# AdaptadorUSBSerialRS232.net
KiCad netlist of a schematic drawn in Altium Designer
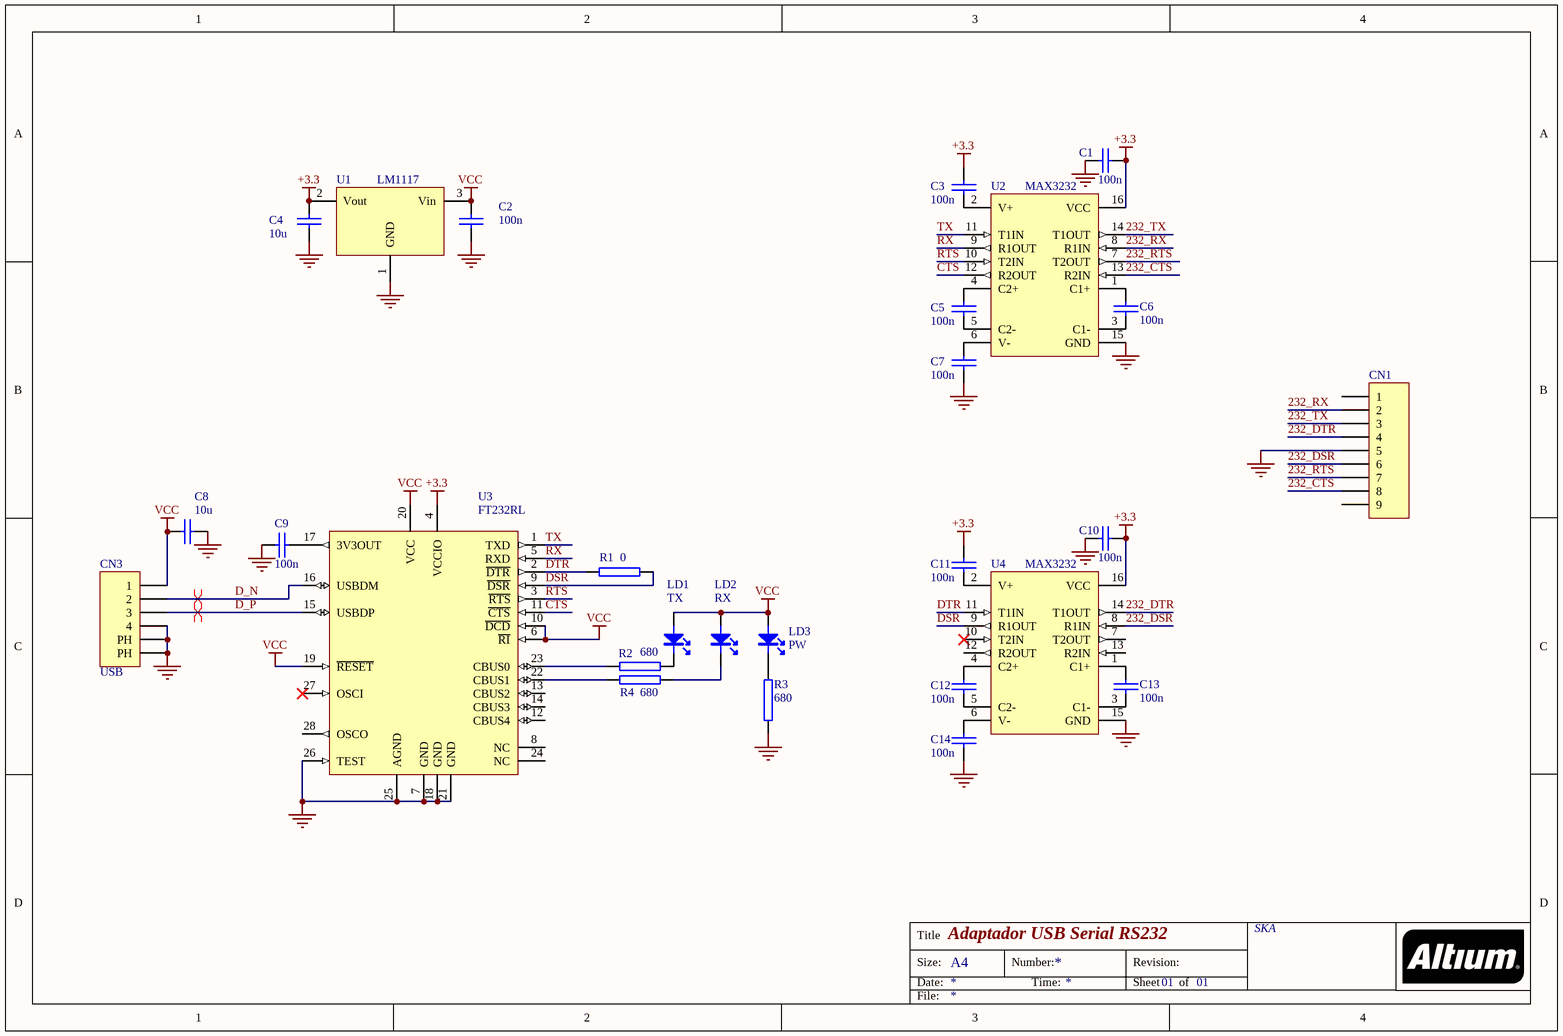
[diagram p0: AdaptadorUSBSerialRS232.SchDoc]

(export (version "E")
  (design (tool "Eeschema 10.0.6"))
  (components
    (comp (ref "C1")
      (value "100n")
      (footprint "0805C")
      (description "CAPACITOR SMD 0805 100nF/50V X7R")
      (libsource (lib "Básicos") (part "CAP"))
    )
    (comp (ref "C2")
      (value "100n")
      (footprint "0805C")
      (description "CAPACITOR SMD 0805 100nF/50V X7R")
      (libsource (lib "Básicos") (part "CAP"))
    )
    (comp (ref "C3")
      (value "100n")
      (footprint "0805C")
      (description "CAPACITOR SMD 0805 100nF/50V X7R")
      (libsource (lib "Básicos") (part "CAP"))
    )
    (comp (ref "C4")
      (value "10u")
      (footprint "0805C")
      (description "CAPACITOR SMD 0805 10UF/6,3V X7R")
      (libsource (lib "") (part "CAP_1"))
    )
    (comp (ref "C5")
      (value "100n")
      (footprint "0805C")
      (description "CAPACITOR SMD 0805 100nF/50V X7R")
      (libsource (lib "Básicos") (part "CAP"))
    )
    (comp (ref "C6")
      (value "100n")
      (footprint "0805C")
      (description "CAPACITOR SMD 0805 100nF/50V X7R")
      (libsource (lib "Básicos") (part "CAP"))
    )
    (comp (ref "C7")
      (value "100n")
      (footprint "0805C")
      (description "CAPACITOR SMD 0805 100nF/50V X7R")
      (libsource (lib "Básicos") (part "CAP"))
    )
    (comp (ref "C8")
      (value "10u")
      (footprint "0805C")
      (description "CAPACITOR SMD 0805 10UF/6,3V X7R")
      (libsource (lib "") (part "CAP_1"))
    )
    (comp (ref "C9")
      (value "100n")
      (footprint "0805C")
      (description "CAPACITOR SMD 0805 100NF/50V X7R")
      (libsource (lib "Básicos") (part "CAP"))
    )
    (comp (ref "C10")
      (value "100n")
      (footprint "0805C")
      (description "CAPACITOR SMD 0805 100nF/50V X7R")
      (libsource (lib "Básicos") (part "CAP"))
    )
    (comp (ref "C11")
      (value "100n")
      (footprint "0805C")
      (description "CAPACITOR SMD 0805 100nF/50V X7R")
      (libsource (lib "Básicos") (part "CAP"))
    )
    (comp (ref "C12")
      (value "100n")
      (footprint "0805C")
      (description "CAPACITOR SMD 0805 100nF/50V X7R")
      (libsource (lib "Básicos") (part "CAP"))
    )
    (comp (ref "C13")
      (value "100n")
      (footprint "0805C")
      (description "CAPACITOR SMD 0805 100nF/50V X7R")
      (libsource (lib "Básicos") (part "CAP"))
    )
    (comp (ref "C14")
      (value "100n")
      (footprint "0805C")
      (description "CAPACITOR SMD 0805 100nF/50V X7R")
      (libsource (lib "Básicos") (part "CAP"))
    )
    (comp (ref "CN1")
      (value "DB9M")
      (footprint "BARRA1X9")
      (description "Espera para DB9 M")
      (libsource (lib "Miscellaneous Connectors") (part "Header 9"))
    )
    (comp (ref "CN3")
      (value "USB")
      (footprint "USB-B 90")
      (description "CONECTOR USB")
      (libsource (lib "Miscellaneous Connectors") (part "Header 6"))
    )
    (comp (ref "LD1")
      (value "RED")
      (footprint "0805L")
      (description "LED 0805 VERMELHO")
      (fields (field (name "FUNCAO") "TX"))
      (libsource (lib "Opto") (part "LED"))
    )
    (comp (ref "LD2")
      (value "RED")
      (footprint "0805L")
      (description "LED 0805 VERMELHO")
      (fields (field (name "FUNCAO") "RX"))
      (libsource (lib "Opto") (part "LED"))
    )
    (comp (ref "LD3")
      (value "RED")
      (footprint "0805L")
      (description "LED 0805 VERMELHO")
      (fields (field (name "FUNCAO") "PW"))
      (libsource (lib "Opto") (part "LED"))
    )
    (comp (ref "R1")
      (value "0")
      (footprint "0805R")
      (description "RESISTOR SMD 0805 0 OHM (JUMPER)")
      (libsource (lib "Básicos") (part "RES"))
    )
    (comp (ref "R2")
      (value "680")
      (footprint "0805R")
      (description "RESISTOR SMD 0805 680 OHM")
      (libsource (lib "Básicos") (part "RES"))
    )
    (comp (ref "R3")
      (value "680")
      (footprint "0805R")
      (description "RESISTOR SMD 0805 680 OHM")
      (libsource (lib "") (part "RES_1"))
    )
    (comp (ref "R4")
      (value "680")
      (footprint "0805R")
      (description "RESISTOR SMD 0805 680 OHM")
      (libsource (lib "Básicos") (part "RES"))
    )
    (comp (ref "U1")
      (value "LM1117")
      (footprint "SOT223")
      (description "REGULADOR LINEAR SMD LM1117MPX-3.3")
      (libsource (lib "Regulador") (part "LM1117"))
    )
    (comp (ref "U2")
      (value "MAX3232")
      (footprint "SO16")
      (description "CI SMD MAX3232 SO16 NARROW")
      (libsource (lib "Interface") (part "MAX232"))
    )
    (comp (ref "U3")
      (value "FT232RL")
      (footprint "SSOP28-175-0.64")
      (description "USB UART FT232RL, SSOP-28, Tray")
      (libsource (lib "altium-import") (part "root_0_COM-UART-FT232R-IL28_"))
    )
    (comp (ref "U4")
      (value "MAX3232")
      (footprint "SO16")
      (description "CI SMD MAX3232 SO16 NARROW")
      (libsource (lib "Interface") (part "MAX232"))
    )
  )
  (nets
    (net (code "1") (name "+3.3") (class "Default")
      (node (ref "C1") (pin "1") (pinfunction "1_1") (pintype "passive"))
      (node (ref "C10") (pin "1") (pinfunction "1_1") (pintype "passive"))
      (node (ref "C11") (pin "1") (pinfunction "1_1") (pintype "passive"))
      (node (ref "C3") (pin "1") (pinfunction "1_1") (pintype "passive"))
      (node (ref "C4") (pin "1") (pinfunction "1_1") (pintype "passive"))
      (node (ref "U1") (pin "2") (pinfunction "Vout_2") (pintype "power_in"))
      (node (ref "U2") (pin "16") (pinfunction "VCC_16") (pintype "power_in"))
      (node (ref "U3") (pin "4") (pinfunction "VCCIO_4") (pintype "power_in"))
      (node (ref "U4") (pin "16") (pinfunction "VCC_16") (pintype "power_in"))
    )
    (net (code "2") (name "/232_CTS") (class "Default")
      (node (ref "CN1") (pin "8") (pinfunction "8_8") (pintype "passive"))
      (node (ref "U2") (pin "13") (pinfunction "R2IN_13") (pintype "input"))
    )
    (net (code "3") (name "/232_DSR") (class "Default")
      (node (ref "CN1") (pin "6") (pinfunction "6_6") (pintype "passive"))
      (node (ref "U4") (pin "8") (pinfunction "R1IN_8") (pintype "input"))
    )
    (net (code "4") (name "/232_DTR") (class "Default")
      (node (ref "CN1") (pin "4") (pinfunction "4_4") (pintype "passive"))
      (node (ref "U4") (pin "14") (pinfunction "T1OUT_14") (pintype "output"))
    )
    (net (code "5") (name "/232_RTS") (class "Default")
      (node (ref "CN1") (pin "7") (pinfunction "7_7") (pintype "passive"))
      (node (ref "U2") (pin "7") (pinfunction "T2OUT_7") (pintype "output"))
    )
    (net (code "6") (name "/232_RX") (class "Default")
      (node (ref "CN1") (pin "2") (pinfunction "2_2") (pintype "passive"))
      (node (ref "U2") (pin "8") (pinfunction "R1IN_8") (pintype "input"))
    )
    (net (code "7") (name "/232_TX") (class "Default")
      (node (ref "CN1") (pin "3") (pinfunction "3_3") (pintype "passive"))
      (node (ref "U2") (pin "14") (pinfunction "T1OUT_14") (pintype "output"))
    )
    (net (code "8") (name "/CTS") (class "Default")
      (node (ref "U2") (pin "12") (pinfunction "R2OUT_12") (pintype "output"))
      (node (ref "U3") (pin "11") (pinfunction "~{CTS}_11") (pintype "input"))
    )
    (net (code "9") (name "/DSR") (class "Default")
      (node (ref "R1") (pin "2") (pinfunction "2_2") (pintype "passive"))
      (node (ref "U3") (pin "9") (pinfunction "~{DSR}_9") (pintype "input"))
      (node (ref "U4") (pin "9") (pinfunction "R1OUT_9") (pintype "output"))
    )
    (net (code "10") (name "/DTR") (class "Default")
      (node (ref "R1") (pin "1") (pinfunction "1_1") (pintype "passive"))
      (node (ref "U3") (pin "2") (pinfunction "~{DTR}_2") (pintype "output"))
      (node (ref "U4") (pin "11") (pinfunction "T1IN_11") (pintype "input"))
    )
    (net (code "11") (name "/D_N") (class "Default")
      (node (ref "CN3") (pin "2") (pinfunction "2_2") (pintype "passive"))
      (node (ref "U3") (pin "16") (pinfunction "USBDM_16") (pintype "bidirectional"))
    )
    (net (code "12") (name "/D_P") (class "Default")
      (node (ref "CN3") (pin "3") (pinfunction "3_3") (pintype "passive"))
      (node (ref "U3") (pin "15") (pinfunction "USBDP_15") (pintype "bidirectional"))
    )
    (net (code "13") (name "/RTS") (class "Default")
      (node (ref "U2") (pin "10") (pinfunction "T2IN_10") (pintype "input"))
      (node (ref "U3") (pin "3") (pinfunction "~{RTS}_3") (pintype "output"))
    )
    (net (code "14") (name "/RX") (class "Default")
      (node (ref "U2") (pin "9") (pinfunction "R1OUT_9") (pintype "output"))
      (node (ref "U3") (pin "5") (pinfunction "RXD_5") (pintype "input"))
    )
    (net (code "15") (name "/TX") (class "Default")
      (node (ref "U2") (pin "11") (pinfunction "T1IN_11") (pintype "input"))
      (node (ref "U3") (pin "1") (pinfunction "TXD_1") (pintype "output"))
    )
    (net (code "16") (name "GND") (class "Default")
      (node (ref "C1") (pin "2") (pinfunction "2_2") (pintype "passive"))
      (node (ref "C10") (pin "2") (pinfunction "2_2") (pintype "passive"))
      (node (ref "C14") (pin "2") (pinfunction "2_2") (pintype "passive"))
      (node (ref "C2") (pin "2") (pinfunction "2_2") (pintype "passive"))
      (node (ref "C4") (pin "2") (pinfunction "2_2") (pintype "passive"))
      (node (ref "C7") (pin "2") (pinfunction "2_2") (pintype "passive"))
      (node (ref "C8") (pin "2") (pinfunction "2_2") (pintype "passive"))
      (node (ref "C9") (pin "2") (pinfunction "2_2") (pintype "passive"))
      (node (ref "CN1") (pin "5") (pinfunction "5_5") (pintype "passive"))
      (node (ref "CN3") (pin "4") (pinfunction "4_4") (pintype "passive"))
      (node (ref "CN3") (pin "PH2") (pinfunction "PH_PH2") (pintype "passive"))
      (node (ref "CN3") (pin "PH3") (pinfunction "PH_PH3") (pintype "passive"))
      (node (ref "R3") (pin "1") (pinfunction "1_1") (pintype "passive"))
      (node (ref "U1") (pin "1") (pinfunction "GND_1") (pintype "power_in"))
      (node (ref "U2") (pin "15") (pinfunction "GND_15") (pintype "power_in"))
      (node (ref "U3") (pin "18") (pinfunction "GND_18") (pintype "power_in"))
      (node (ref "U3") (pin "21") (pinfunction "GND_21") (pintype "power_in"))
      (node (ref "U3") (pin "25") (pinfunction "AGND_25") (pintype "power_in"))
      (node (ref "U3") (pin "26") (pinfunction "TEST_26") (pintype "input"))
      (node (ref "U3") (pin "7") (pinfunction "GND_7") (pintype "power_in"))
      (node (ref "U4") (pin "15") (pinfunction "GND_15") (pintype "power_in"))
    )
    (net (code "17") (name "Net-(LD1-K)") (class "Default")
      (node (ref "LD1") (pin "1") (pinfunction "K_1") (pintype "passive"))
      (node (ref "R2") (pin "2") (pinfunction "2_2") (pintype "passive"))
    )
    (net (code "18") (name "Net-(LD2-K)") (class "Default")
      (node (ref "LD2") (pin "1") (pinfunction "K_1") (pintype "passive"))
      (node (ref "R4") (pin "2") (pinfunction "2_2") (pintype "passive"))
    )
    (net (code "19") (name "Net-(LD3-K)") (class "Default")
      (node (ref "LD3") (pin "1") (pinfunction "K_1") (pintype "passive"))
      (node (ref "R3") (pin "2") (pinfunction "2_2") (pintype "passive"))
    )
    (net (code "20") (name "Net-(U2-C1+)") (class "Default")
      (node (ref "C6") (pin "1") (pinfunction "1_1") (pintype "passive"))
      (node (ref "U2") (pin "1") (pinfunction "C1+_1") (pintype "passive"))
    )
    (net (code "21") (name "Net-(U2-C1-)") (class "Default")
      (node (ref "C6") (pin "2") (pinfunction "2_2") (pintype "passive"))
      (node (ref "U2") (pin "3") (pinfunction "C1-_3") (pintype "passive"))
    )
    (net (code "22") (name "Net-(U2-C2+)") (class "Default")
      (node (ref "C5") (pin "1") (pinfunction "1_1") (pintype "passive"))
      (node (ref "U2") (pin "4") (pinfunction "C2+_4") (pintype "passive"))
    )
    (net (code "23") (name "Net-(U2-C2-)") (class "Default")
      (node (ref "C5") (pin "2") (pinfunction "2_2") (pintype "passive"))
      (node (ref "U2") (pin "5") (pinfunction "C2-_5") (pintype "passive"))
    )
    (net (code "24") (name "Net-(U2-V+)") (class "Default")
      (node (ref "C3") (pin "2") (pinfunction "2_2") (pintype "passive"))
      (node (ref "U2") (pin "2") (pinfunction "V+_2") (pintype "power_in"))
    )
    (net (code "25") (name "Net-(U2-V-)") (class "Default")
      (node (ref "C7") (pin "1") (pinfunction "1_1") (pintype "passive"))
      (node (ref "U2") (pin "6") (pinfunction "V-_6") (pintype "power_in"))
    )
    (net (code "26") (name "Net-(U3-3V3OUT)") (class "Default")
      (node (ref "C9") (pin "1") (pinfunction "1_1") (pintype "passive"))
      (node (ref "U3") (pin "17") (pinfunction "3V3OUT_17") (pintype "output"))
    )
    (net (code "27") (name "Net-(U3-CBUS0)") (class "Default")
      (node (ref "R2") (pin "1") (pinfunction "1_1") (pintype "passive"))
      (node (ref "U3") (pin "23") (pinfunction "CBUS0_23") (pintype "bidirectional"))
    )
    (net (code "28") (name "Net-(U3-CBUS1)") (class "Default")
      (node (ref "R4") (pin "1") (pinfunction "1_1") (pintype "passive"))
      (node (ref "U3") (pin "22") (pinfunction "CBUS1_22") (pintype "bidirectional"))
    )
    (net (code "29") (name "Net-(U4-C1+)") (class "Default")
      (node (ref "C13") (pin "1") (pinfunction "1_1") (pintype "passive"))
      (node (ref "U4") (pin "1") (pinfunction "C1+_1") (pintype "passive"))
    )
    (net (code "30") (name "Net-(U4-C1-)") (class "Default")
      (node (ref "C13") (pin "2") (pinfunction "2_2") (pintype "passive"))
      (node (ref "U4") (pin "3") (pinfunction "C1-_3") (pintype "passive"))
    )
    (net (code "31") (name "Net-(U4-C2+)") (class "Default")
      (node (ref "C12") (pin "1") (pinfunction "1_1") (pintype "passive"))
      (node (ref "U4") (pin "4") (pinfunction "C2+_4") (pintype "passive"))
    )
    (net (code "32") (name "Net-(U4-C2-)") (class "Default")
      (node (ref "C12") (pin "2") (pinfunction "2_2") (pintype "passive"))
      (node (ref "U4") (pin "5") (pinfunction "C2-_5") (pintype "passive"))
    )
    (net (code "33") (name "Net-(U4-V+)") (class "Default")
      (node (ref "C11") (pin "2") (pinfunction "2_2") (pintype "passive"))
      (node (ref "U4") (pin "2") (pinfunction "V+_2") (pintype "power_in"))
    )
    (net (code "34") (name "Net-(U4-V-)") (class "Default")
      (node (ref "C14") (pin "1") (pinfunction "1_1") (pintype "passive"))
      (node (ref "U4") (pin "6") (pinfunction "V-_6") (pintype "power_in"))
    )
    (net (code "35") (name "VCC") (class "Default")
      (node (ref "C2") (pin "1") (pinfunction "1_1") (pintype "passive"))
      (node (ref "C8") (pin "1") (pinfunction "1_1") (pintype "passive"))
      (node (ref "CN3") (pin "1") (pinfunction "1_1") (pintype "passive"))
      (node (ref "LD1") (pin "2") (pinfunction "A_2") (pintype "passive"))
      (node (ref "LD2") (pin "2") (pinfunction "A_2") (pintype "passive"))
      (node (ref "LD3") (pin "2") (pinfunction "A_2") (pintype "passive"))
      (node (ref "U1") (pin "3") (pinfunction "Vin_3") (pintype "power_in"))
      (node (ref "U3") (pin "10") (pinfunction "~{DCD}_10") (pintype "input"))
      (node (ref "U3") (pin "19") (pinfunction "~{RESET}_19") (pintype "input"))
      (node (ref "U3") (pin "20") (pinfunction "VCC_20") (pintype "power_in"))
      (node (ref "U3") (pin "6") (pinfunction "~{RI}_6") (pintype "input"))
    )
    (net (code "36") (name "unconnected-(CN1-Pad1)") (class "Default")
      (node (ref "CN1") (pin "1") (pinfunction "1_1") (pintype "passive"))
    )
    (net (code "37") (name "unconnected-(CN1-Pad9)") (class "Default")
      (node (ref "CN1") (pin "9") (pinfunction "9_9") (pintype "passive"))
    )
    (net (code "38") (name "unconnected-(U3-CBUS2-Pad13)") (class "Default")
      (node (ref "U3") (pin "13") (pinfunction "CBUS2_13") (pintype "bidirectional"))
    )
    (net (code "39") (name "unconnected-(U3-CBUS3-Pad14)") (class "Default")
      (node (ref "U3") (pin "14") (pinfunction "CBUS3_14") (pintype "bidirectional"))
    )
    (net (code "40") (name "unconnected-(U3-CBUS4-Pad12)") (class "Default")
      (node (ref "U3") (pin "12") (pinfunction "CBUS4_12") (pintype "bidirectional"))
    )
    (net (code "41") (name "unconnected-(U3-NC-Pad8)") (class "Default")
      (node (ref "U3") (pin "8") (pinfunction "NC_8") (pintype "passive"))
    )
    (net (code "42") (name "unconnected-(U3-NC-Pad24)") (class "Default")
      (node (ref "U3") (pin "24") (pinfunction "NC_24") (pintype "passive"))
    )
    (net (code "43") (name "unconnected-(U3-OSCI-Pad27)") (class "Default")
      (node (ref "U3") (pin "27") (pinfunction "OSCI_27") (pintype "input+no_connect"))
    )
    (net (code "44") (name "unconnected-(U3-OSCO-Pad28)") (class "Default")
      (node (ref "U3") (pin "28") (pinfunction "OSCO_28") (pintype "output"))
    )
    (net (code "45") (name "unconnected-(U4-R2IN-Pad13)") (class "Default")
      (node (ref "U4") (pin "13") (pinfunction "R2IN_13") (pintype "input"))
    )
    (net (code "46") (name "unconnected-(U4-R2OUT-Pad12)") (class "Default")
      (node (ref "U4") (pin "12") (pinfunction "R2OUT_12") (pintype "output"))
    )
    (net (code "47") (name "unconnected-(U4-T2IN-Pad10)") (class "Default")
      (node (ref "U4") (pin "10") (pinfunction "T2IN_10") (pintype "input+no_connect"))
    )
    (net (code "48") (name "unconnected-(U4-T2OUT-Pad7)") (class "Default")
      (node (ref "U4") (pin "7") (pinfunction "T2OUT_7") (pintype "output"))
    )
  )
)
